# ConstantLED.net
KiCad netlist of a schematic drawn in Altium Designer
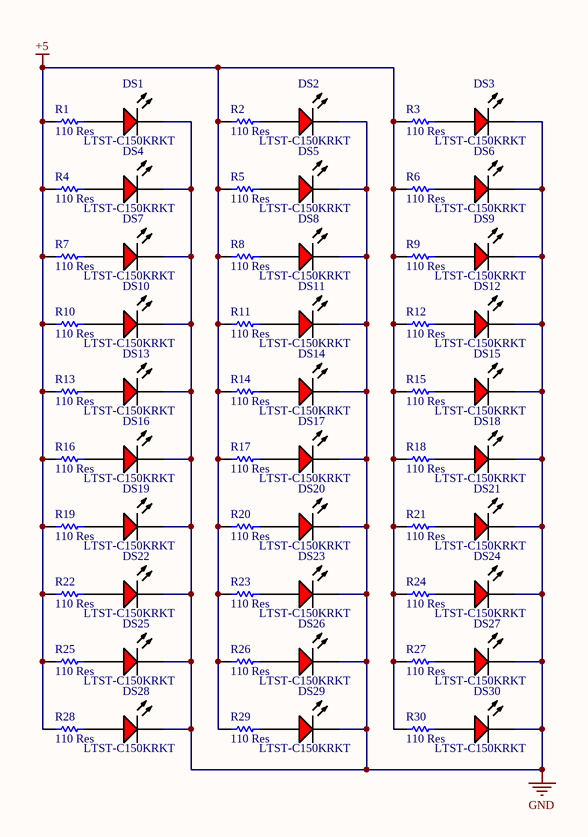
[diagram p0: ConstantLED.SchDoc]

(export (version "E")
  (design (tool "Eeschema 10.0.6"))
  (components
    (comp (ref "DS1")
      (value "LTST-C150KRKT")
      (footprint "LTST-C150KRKT_V")
      (description "LED Red, 62.5 mW, 50 mA, -30 to 85 degC, 2-Pin SMD, RoHS, Tape and Reel")
      (fields (field (name "MANUFACTURER") "Lite-On"))
      (libsource (lib "Altium Content Vault") (part "LED-RED-AK-2"))
    )
    (comp (ref "DS2")
      (value "LTST-C150KRKT")
      (footprint "LTST-C150KRKT_V")
      (description "LED Red, 62.5 mW, 50 mA, -30 to 85 degC, 2-Pin SMD, RoHS, Tape and Reel")
      (fields (field (name "MANUFACTURER") "Lite-On"))
      (libsource (lib "Altium Content Vault") (part "LED-RED-AK-2"))
    )
    (comp (ref "DS3")
      (value "LTST-C150KRKT")
      (footprint "LTST-C150KRKT_V")
      (description "LED Red, 62.5 mW, 50 mA, -30 to 85 degC, 2-Pin SMD, RoHS, Tape and Reel")
      (fields (field (name "MANUFACTURER") "Lite-On"))
      (libsource (lib "Altium Content Vault") (part "LED-RED-AK-2"))
    )
    (comp (ref "DS4")
      (value "LTST-C150KRKT")
      (footprint "LTST-C150KRKT_V")
      (description "LED Red, 62.5 mW, 50 mA, -30 to 85 degC, 2-Pin SMD, RoHS, Tape and Reel")
      (fields (field (name "MANUFACTURER") "Lite-On"))
      (libsource (lib "Altium Content Vault") (part "LED-RED-AK-2"))
    )
    (comp (ref "DS5")
      (value "LTST-C150KRKT")
      (footprint "LTST-C150KRKT_V")
      (description "LED Red, 62.5 mW, 50 mA, -30 to 85 degC, 2-Pin SMD, RoHS, Tape and Reel")
      (fields (field (name "MANUFACTURER") "Lite-On"))
      (libsource (lib "Altium Content Vault") (part "LED-RED-AK-2"))
    )
    (comp (ref "DS6")
      (value "LTST-C150KRKT")
      (footprint "LTST-C150KRKT_V")
      (description "LED Red, 62.5 mW, 50 mA, -30 to 85 degC, 2-Pin SMD, RoHS, Tape and Reel")
      (fields (field (name "MANUFACTURER") "Lite-On"))
      (libsource (lib "Altium Content Vault") (part "LED-RED-AK-2"))
    )
    (comp (ref "DS7")
      (value "LTST-C150KRKT")
      (footprint "LTST-C150KRKT_V")
      (description "LED Red, 62.5 mW, 50 mA, -30 to 85 degC, 2-Pin SMD, RoHS, Tape and Reel")
      (fields (field (name "MANUFACTURER") "Lite-On"))
      (libsource (lib "Altium Content Vault") (part "LED-RED-AK-2"))
    )
    (comp (ref "DS8")
      (value "LTST-C150KRKT")
      (footprint "LTST-C150KRKT_V")
      (description "LED Red, 62.5 mW, 50 mA, -30 to 85 degC, 2-Pin SMD, RoHS, Tape and Reel")
      (fields (field (name "MANUFACTURER") "Lite-On"))
      (libsource (lib "Altium Content Vault") (part "LED-RED-AK-2"))
    )
    (comp (ref "DS9")
      (value "LTST-C150KRKT")
      (footprint "LTST-C150KRKT_V")
      (description "LED Red, 62.5 mW, 50 mA, -30 to 85 degC, 2-Pin SMD, RoHS, Tape and Reel")
      (fields (field (name "MANUFACTURER") "Lite-On"))
      (libsource (lib "Altium Content Vault") (part "LED-RED-AK-2"))
    )
    (comp (ref "DS10")
      (value "LTST-C150KRKT")
      (footprint "LTST-C150KRKT_V")
      (description "LED Red, 62.5 mW, 50 mA, -30 to 85 degC, 2-Pin SMD, RoHS, Tape and Reel")
      (fields (field (name "MANUFACTURER") "Lite-On"))
      (libsource (lib "Altium Content Vault") (part "LED-RED-AK-2"))
    )
    (comp (ref "DS11")
      (value "LTST-C150KRKT")
      (footprint "LTST-C150KRKT_V")
      (description "LED Red, 62.5 mW, 50 mA, -30 to 85 degC, 2-Pin SMD, RoHS, Tape and Reel")
      (fields (field (name "MANUFACTURER") "Lite-On"))
      (libsource (lib "Altium Content Vault") (part "LED-RED-AK-2"))
    )
    (comp (ref "DS12")
      (value "LTST-C150KRKT")
      (footprint "LTST-C150KRKT_V")
      (description "LED Red, 62.5 mW, 50 mA, -30 to 85 degC, 2-Pin SMD, RoHS, Tape and Reel")
      (fields (field (name "MANUFACTURER") "Lite-On"))
      (libsource (lib "Altium Content Vault") (part "LED-RED-AK-2"))
    )
    (comp (ref "DS13")
      (value "LTST-C150KRKT")
      (footprint "LTST-C150KRKT_V")
      (description "LED Red, 62.5 mW, 50 mA, -30 to 85 degC, 2-Pin SMD, RoHS, Tape and Reel")
      (fields (field (name "MANUFACTURER") "Lite-On"))
      (libsource (lib "Altium Content Vault") (part "LED-RED-AK-2"))
    )
    (comp (ref "DS14")
      (value "LTST-C150KRKT")
      (footprint "LTST-C150KRKT_V")
      (description "LED Red, 62.5 mW, 50 mA, -30 to 85 degC, 2-Pin SMD, RoHS, Tape and Reel")
      (fields (field (name "MANUFACTURER") "Lite-On"))
      (libsource (lib "Altium Content Vault") (part "LED-RED-AK-2"))
    )
    (comp (ref "DS15")
      (value "LTST-C150KRKT")
      (footprint "LTST-C150KRKT_V")
      (description "LED Red, 62.5 mW, 50 mA, -30 to 85 degC, 2-Pin SMD, RoHS, Tape and Reel")
      (fields (field (name "MANUFACTURER") "Lite-On"))
      (libsource (lib "Altium Content Vault") (part "LED-RED-AK-2"))
    )
    (comp (ref "DS16")
      (value "LTST-C150KRKT")
      (footprint "LTST-C150KRKT_V")
      (description "LED Red, 62.5 mW, 50 mA, -30 to 85 degC, 2-Pin SMD, RoHS, Tape and Reel")
      (fields (field (name "MANUFACTURER") "Lite-On"))
      (libsource (lib "Altium Content Vault") (part "LED-RED-AK-2"))
    )
    (comp (ref "DS17")
      (value "LTST-C150KRKT")
      (footprint "LTST-C150KRKT_V")
      (description "LED Red, 62.5 mW, 50 mA, -30 to 85 degC, 2-Pin SMD, RoHS, Tape and Reel")
      (fields (field (name "MANUFACTURER") "Lite-On"))
      (libsource (lib "Altium Content Vault") (part "LED-RED-AK-2"))
    )
    (comp (ref "DS18")
      (value "LTST-C150KRKT")
      (footprint "LTST-C150KRKT_V")
      (description "LED Red, 62.5 mW, 50 mA, -30 to 85 degC, 2-Pin SMD, RoHS, Tape and Reel")
      (fields (field (name "MANUFACTURER") "Lite-On"))
      (libsource (lib "Altium Content Vault") (part "LED-RED-AK-2"))
    )
    (comp (ref "DS19")
      (value "LTST-C150KRKT")
      (footprint "LTST-C150KRKT_V")
      (description "LED Red, 62.5 mW, 50 mA, -30 to 85 degC, 2-Pin SMD, RoHS, Tape and Reel")
      (fields (field (name "MANUFACTURER") "Lite-On"))
      (libsource (lib "Altium Content Vault") (part "LED-RED-AK-2"))
    )
    (comp (ref "DS20")
      (value "LTST-C150KRKT")
      (footprint "LTST-C150KRKT_V")
      (description "LED Red, 62.5 mW, 50 mA, -30 to 85 degC, 2-Pin SMD, RoHS, Tape and Reel")
      (fields (field (name "MANUFACTURER") "Lite-On"))
      (libsource (lib "Altium Content Vault") (part "LED-RED-AK-2"))
    )
    (comp (ref "DS21")
      (value "LTST-C150KRKT")
      (footprint "LTST-C150KRKT_V")
      (description "LED Red, 62.5 mW, 50 mA, -30 to 85 degC, 2-Pin SMD, RoHS, Tape and Reel")
      (fields (field (name "MANUFACTURER") "Lite-On"))
      (libsource (lib "Altium Content Vault") (part "LED-RED-AK-2"))
    )
    (comp (ref "DS22")
      (value "LTST-C150KRKT")
      (footprint "LTST-C150KRKT_V")
      (description "LED Red, 62.5 mW, 50 mA, -30 to 85 degC, 2-Pin SMD, RoHS, Tape and Reel")
      (fields (field (name "MANUFACTURER") "Lite-On"))
      (libsource (lib "Altium Content Vault") (part "LED-RED-AK-2"))
    )
    (comp (ref "DS23")
      (value "LTST-C150KRKT")
      (footprint "LTST-C150KRKT_V")
      (description "LED Red, 62.5 mW, 50 mA, -30 to 85 degC, 2-Pin SMD, RoHS, Tape and Reel")
      (fields (field (name "MANUFACTURER") "Lite-On"))
      (libsource (lib "Altium Content Vault") (part "LED-RED-AK-2"))
    )
    (comp (ref "DS24")
      (value "LTST-C150KRKT")
      (footprint "LTST-C150KRKT_V")
      (description "LED Red, 62.5 mW, 50 mA, -30 to 85 degC, 2-Pin SMD, RoHS, Tape and Reel")
      (fields (field (name "MANUFACTURER") "Lite-On"))
      (libsource (lib "Altium Content Vault") (part "LED-RED-AK-2"))
    )
    (comp (ref "DS25")
      (value "LTST-C150KRKT")
      (footprint "LTST-C150KRKT_V")
      (description "LED Red, 62.5 mW, 50 mA, -30 to 85 degC, 2-Pin SMD, RoHS, Tape and Reel")
      (fields (field (name "MANUFACTURER") "Lite-On"))
      (libsource (lib "Altium Content Vault") (part "LED-RED-AK-2"))
    )
    (comp (ref "DS26")
      (value "LTST-C150KRKT")
      (footprint "LTST-C150KRKT_V")
      (description "LED Red, 62.5 mW, 50 mA, -30 to 85 degC, 2-Pin SMD, RoHS, Tape and Reel")
      (fields (field (name "MANUFACTURER") "Lite-On"))
      (libsource (lib "Altium Content Vault") (part "LED-RED-AK-2"))
    )
    (comp (ref "DS27")
      (value "LTST-C150KRKT")
      (footprint "LTST-C150KRKT_V")
      (description "LED Red, 62.5 mW, 50 mA, -30 to 85 degC, 2-Pin SMD, RoHS, Tape and Reel")
      (fields (field (name "MANUFACTURER") "Lite-On"))
      (libsource (lib "Altium Content Vault") (part "LED-RED-AK-2"))
    )
    (comp (ref "DS28")
      (value "LTST-C150KRKT")
      (footprint "LTST-C150KRKT_V")
      (description "LED Red, 62.5 mW, 50 mA, -30 to 85 degC, 2-Pin SMD, RoHS, Tape and Reel")
      (fields (field (name "MANUFACTURER") "Lite-On"))
      (libsource (lib "Altium Content Vault") (part "LED-RED-AK-2"))
    )
    (comp (ref "DS29")
      (value "LTST-C150KRKT")
      (footprint "LTST-C150KRKT_V")
      (description "LED Red, 62.5 mW, 50 mA, -30 to 85 degC, 2-Pin SMD, RoHS, Tape and Reel")
      (fields (field (name "MANUFACTURER") "Lite-On"))
      (libsource (lib "Altium Content Vault") (part "LED-RED-AK-2"))
    )
    (comp (ref "DS30")
      (value "LTST-C150KRKT")
      (footprint "LTST-C150KRKT_V")
      (description "LED Red, 62.5 mW, 50 mA, -30 to 85 degC, 2-Pin SMD, RoHS, Tape and Reel")
      (fields (field (name "MANUFACTURER") "Lite-On"))
      (libsource (lib "Altium Content Vault") (part "LED-RED-AK-2"))
    )
    (comp (ref "R1")
      (value "110 Res")
      (footprint "RESC3216X70X50LL05T20")
      (fields (field (name "PART NUMBER") "ERJ-8ENF1100V") (field (name "MANUFACTURER") "Panasonic"))
      (libsource (lib "Altium Content Vault") (part "RES"))
    )
    (comp (ref "R2")
      (value "110 Res")
      (footprint "RESC3216X70X50LL05T20")
      (fields (field (name "PART NUMBER") "ERJ-8ENF1100V") (field (name "MANUFACTURER") "Panasonic"))
      (libsource (lib "Altium Content Vault") (part "RES"))
    )
    (comp (ref "R3")
      (value "110 Res")
      (footprint "RESC3216X70X50LL05T20")
      (fields (field (name "PART NUMBER") "ERJ-8ENF1100V") (field (name "MANUFACTURER") "Panasonic"))
      (libsource (lib "Altium Content Vault") (part "RES"))
    )
    (comp (ref "R4")
      (value "110 Res")
      (footprint "RESC3216X70X50LL05T20")
      (fields (field (name "PART NUMBER") "ERJ-8ENF1100V") (field (name "MANUFACTURER") "Panasonic"))
      (libsource (lib "Altium Content Vault") (part "RES"))
    )
    (comp (ref "R5")
      (value "110 Res")
      (footprint "RESC3216X70X50LL05T20")
      (fields (field (name "PART NUMBER") "ERJ-8ENF1100V") (field (name "MANUFACTURER") "Panasonic"))
      (libsource (lib "Altium Content Vault") (part "RES"))
    )
    (comp (ref "R6")
      (value "110 Res")
      (footprint "RESC3216X70X50LL05T20")
      (fields (field (name "PART NUMBER") "ERJ-8ENF1100V") (field (name "MANUFACTURER") "Panasonic"))
      (libsource (lib "Altium Content Vault") (part "RES"))
    )
    (comp (ref "R7")
      (value "110 Res")
      (footprint "RESC3216X70X50LL05T20")
      (fields (field (name "PART NUMBER") "ERJ-8ENF1100V") (field (name "MANUFACTURER") "Panasonic"))
      (libsource (lib "Altium Content Vault") (part "RES"))
    )
    (comp (ref "R8")
      (value "110 Res")
      (footprint "RESC3216X70X50LL05T20")
      (fields (field (name "PART NUMBER") "ERJ-8ENF1100V") (field (name "MANUFACTURER") "Panasonic"))
      (libsource (lib "Altium Content Vault") (part "RES"))
    )
    (comp (ref "R9")
      (value "110 Res")
      (footprint "RESC3216X70X50LL05T20")
      (fields (field (name "PART NUMBER") "ERJ-8ENF1100V") (field (name "MANUFACTURER") "Panasonic"))
      (libsource (lib "Altium Content Vault") (part "RES"))
    )
    (comp (ref "R10")
      (value "110 Res")
      (footprint "RESC3216X70X50LL05T20")
      (fields (field (name "PART NUMBER") "ERJ-8ENF1100V") (field (name "MANUFACTURER") "Panasonic"))
      (libsource (lib "Altium Content Vault") (part "RES"))
    )
    (comp (ref "R11")
      (value "110 Res")
      (footprint "RESC3216X70X50LL05T20")
      (fields (field (name "PART NUMBER") "ERJ-8ENF1100V") (field (name "MANUFACTURER") "Panasonic"))
      (libsource (lib "Altium Content Vault") (part "RES"))
    )
    (comp (ref "R12")
      (value "110 Res")
      (footprint "RESC3216X70X50LL05T20")
      (fields (field (name "PART NUMBER") "ERJ-8ENF1100V") (field (name "MANUFACTURER") "Panasonic"))
      (libsource (lib "Altium Content Vault") (part "RES"))
    )
    (comp (ref "R13")
      (value "110 Res")
      (footprint "RESC3216X70X50LL05T20")
      (fields (field (name "PART NUMBER") "ERJ-8ENF1100V") (field (name "MANUFACTURER") "Panasonic"))
      (libsource (lib "Altium Content Vault") (part "RES"))
    )
    (comp (ref "R14")
      (value "110 Res")
      (footprint "RESC3216X70X50LL05T20")
      (fields (field (name "PART NUMBER") "ERJ-8ENF1100V") (field (name "MANUFACTURER") "Panasonic"))
      (libsource (lib "Altium Content Vault") (part "RES"))
    )
    (comp (ref "R15")
      (value "110 Res")
      (footprint "RESC3216X70X50LL05T20")
      (fields (field (name "PART NUMBER") "ERJ-8ENF1100V") (field (name "MANUFACTURER") "Panasonic"))
      (libsource (lib "Altium Content Vault") (part "RES"))
    )
    (comp (ref "R16")
      (value "110 Res")
      (footprint "RESC3216X70X50LL05T20")
      (fields (field (name "PART NUMBER") "ERJ-8ENF1100V") (field (name "MANUFACTURER") "Panasonic"))
      (libsource (lib "Altium Content Vault") (part "RES"))
    )
    (comp (ref "R17")
      (value "110 Res")
      (footprint "RESC3216X70X50LL05T20")
      (fields (field (name "PART NUMBER") "ERJ-8ENF1100V") (field (name "MANUFACTURER") "Panasonic"))
      (libsource (lib "Altium Content Vault") (part "RES"))
    )
    (comp (ref "R18")
      (value "110 Res")
      (footprint "RESC3216X70X50LL05T20")
      (fields (field (name "PART NUMBER") "ERJ-8ENF1100V") (field (name "MANUFACTURER") "Panasonic"))
      (libsource (lib "Altium Content Vault") (part "RES"))
    )
    (comp (ref "R19")
      (value "110 Res")
      (footprint "RESC3216X70X50LL05T20")
      (fields (field (name "PART NUMBER") "ERJ-8ENF1100V") (field (name "MANUFACTURER") "Panasonic"))
      (libsource (lib "Altium Content Vault") (part "RES"))
    )
    (comp (ref "R20")
      (value "110 Res")
      (footprint "RESC3216X70X50LL05T20")
      (fields (field (name "PART NUMBER") "ERJ-8ENF1100V") (field (name "MANUFACTURER") "Panasonic"))
      (libsource (lib "Altium Content Vault") (part "RES"))
    )
    (comp (ref "R21")
      (value "110 Res")
      (footprint "RESC3216X70X50LL05T20")
      (fields (field (name "PART NUMBER") "ERJ-8ENF1100V") (field (name "MANUFACTURER") "Panasonic"))
      (libsource (lib "Altium Content Vault") (part "RES"))
    )
    (comp (ref "R22")
      (value "110 Res")
      (footprint "RESC3216X70X50LL05T20")
      (fields (field (name "PART NUMBER") "ERJ-8ENF1100V") (field (name "MANUFACTURER") "Panasonic"))
      (libsource (lib "Altium Content Vault") (part "RES"))
    )
    (comp (ref "R23")
      (value "110 Res")
      (footprint "RESC3216X70X50LL05T20")
      (fields (field (name "PART NUMBER") "ERJ-8ENF1100V") (field (name "MANUFACTURER") "Panasonic"))
      (libsource (lib "Altium Content Vault") (part "RES"))
    )
    (comp (ref "R24")
      (value "110 Res")
      (footprint "RESC3216X70X50LL05T20")
      (fields (field (name "PART NUMBER") "ERJ-8ENF1100V") (field (name "MANUFACTURER") "Panasonic"))
      (libsource (lib "Altium Content Vault") (part "RES"))
    )
    (comp (ref "R25")
      (value "110 Res")
      (footprint "RESC3216X70X50LL05T20")
      (fields (field (name "PART NUMBER") "ERJ-8ENF1100V") (field (name "MANUFACTURER") "Panasonic"))
      (libsource (lib "Altium Content Vault") (part "RES"))
    )
    (comp (ref "R26")
      (value "110 Res")
      (footprint "RESC3216X70X50LL05T20")
      (fields (field (name "PART NUMBER") "ERJ-8ENF1100V") (field (name "MANUFACTURER") "Panasonic"))
      (libsource (lib "Altium Content Vault") (part "RES"))
    )
    (comp (ref "R27")
      (value "110 Res")
      (footprint "RESC3216X70X50LL05T20")
      (fields (field (name "PART NUMBER") "ERJ-8ENF1100V") (field (name "MANUFACTURER") "Panasonic"))
      (libsource (lib "Altium Content Vault") (part "RES"))
    )
    (comp (ref "R28")
      (value "110 Res")
      (footprint "RESC3216X70X50LL05T20")
      (fields (field (name "PART NUMBER") "ERJ-8ENF1100V") (field (name "MANUFACTURER") "Panasonic"))
      (libsource (lib "Altium Content Vault") (part "RES"))
    )
    (comp (ref "R29")
      (value "110 Res")
      (footprint "RESC3216X70X50LL05T20")
      (fields (field (name "PART NUMBER") "ERJ-8ENF1100V") (field (name "MANUFACTURER") "Panasonic"))
      (libsource (lib "Altium Content Vault") (part "RES"))
    )
    (comp (ref "R30")
      (value "110 Res")
      (footprint "RESC3216X70X50LL05T20")
      (fields (field (name "PART NUMBER") "ERJ-8ENF1100V") (field (name "MANUFACTURER") "Panasonic"))
      (libsource (lib "Altium Content Vault") (part "RES"))
    )
  )
  (nets
    (net (code "1") (name "+5") (class "Default")
      (node (ref "R1") (pin "1") (pinfunction "1_1") (pintype "passive"))
      (node (ref "R10") (pin "1") (pinfunction "1_1") (pintype "passive"))
      (node (ref "R11") (pin "1") (pinfunction "1_1") (pintype "passive"))
      (node (ref "R12") (pin "1") (pinfunction "1_1") (pintype "passive"))
      (node (ref "R13") (pin "1") (pinfunction "1_1") (pintype "passive"))
      (node (ref "R14") (pin "1") (pinfunction "1_1") (pintype "passive"))
      (node (ref "R15") (pin "1") (pinfunction "1_1") (pintype "passive"))
      (node (ref "R16") (pin "1") (pinfunction "1_1") (pintype "passive"))
      (node (ref "R17") (pin "1") (pinfunction "1_1") (pintype "passive"))
      (node (ref "R18") (pin "1") (pinfunction "1_1") (pintype "passive"))
      (node (ref "R19") (pin "1") (pinfunction "1_1") (pintype "passive"))
      (node (ref "R2") (pin "1") (pinfunction "1_1") (pintype "passive"))
      (node (ref "R20") (pin "1") (pinfunction "1_1") (pintype "passive"))
      (node (ref "R21") (pin "1") (pinfunction "1_1") (pintype "passive"))
      (node (ref "R22") (pin "1") (pinfunction "1_1") (pintype "passive"))
      (node (ref "R23") (pin "1") (pinfunction "1_1") (pintype "passive"))
      (node (ref "R24") (pin "1") (pinfunction "1_1") (pintype "passive"))
      (node (ref "R25") (pin "1") (pinfunction "1_1") (pintype "passive"))
      (node (ref "R26") (pin "1") (pinfunction "1_1") (pintype "passive"))
      (node (ref "R27") (pin "1") (pinfunction "1_1") (pintype "passive"))
      (node (ref "R28") (pin "1") (pinfunction "1_1") (pintype "passive"))
      (node (ref "R29") (pin "1") (pinfunction "1_1") (pintype "passive"))
      (node (ref "R3") (pin "1") (pinfunction "1_1") (pintype "passive"))
      (node (ref "R30") (pin "1") (pinfunction "1_1") (pintype "passive"))
      (node (ref "R4") (pin "1") (pinfunction "1_1") (pintype "passive"))
      (node (ref "R5") (pin "1") (pinfunction "1_1") (pintype "passive"))
      (node (ref "R6") (pin "1") (pinfunction "1_1") (pintype "passive"))
      (node (ref "R7") (pin "1") (pinfunction "1_1") (pintype "passive"))
      (node (ref "R8") (pin "1") (pinfunction "1_1") (pintype "passive"))
      (node (ref "R9") (pin "1") (pinfunction "1_1") (pintype "passive"))
    )
    (net (code "2") (name "GND") (class "Default")
      (node (ref "DS1") (pin "2") (pinfunction "K_2") (pintype "passive"))
      (node (ref "DS10") (pin "2") (pinfunction "K_2") (pintype "passive"))
      (node (ref "DS11") (pin "2") (pinfunction "K_2") (pintype "passive"))
      (node (ref "DS12") (pin "2") (pinfunction "K_2") (pintype "passive"))
      (node (ref "DS13") (pin "2") (pinfunction "K_2") (pintype "passive"))
      (node (ref "DS14") (pin "2") (pinfunction "K_2") (pintype "passive"))
      (node (ref "DS15") (pin "2") (pinfunction "K_2") (pintype "passive"))
      (node (ref "DS16") (pin "2") (pinfunction "K_2") (pintype "passive"))
      (node (ref "DS17") (pin "2") (pinfunction "K_2") (pintype "passive"))
      (node (ref "DS18") (pin "2") (pinfunction "K_2") (pintype "passive"))
      (node (ref "DS19") (pin "2") (pinfunction "K_2") (pintype "passive"))
      (node (ref "DS2") (pin "2") (pinfunction "K_2") (pintype "passive"))
      (node (ref "DS20") (pin "2") (pinfunction "K_2") (pintype "passive"))
      (node (ref "DS21") (pin "2") (pinfunction "K_2") (pintype "passive"))
      (node (ref "DS22") (pin "2") (pinfunction "K_2") (pintype "passive"))
      (node (ref "DS23") (pin "2") (pinfunction "K_2") (pintype "passive"))
      (node (ref "DS24") (pin "2") (pinfunction "K_2") (pintype "passive"))
      (node (ref "DS25") (pin "2") (pinfunction "K_2") (pintype "passive"))
      (node (ref "DS26") (pin "2") (pinfunction "K_2") (pintype "passive"))
      (node (ref "DS27") (pin "2") (pinfunction "K_2") (pintype "passive"))
      (node (ref "DS28") (pin "2") (pinfunction "K_2") (pintype "passive"))
      (node (ref "DS29") (pin "2") (pinfunction "K_2") (pintype "passive"))
      (node (ref "DS3") (pin "2") (pinfunction "K_2") (pintype "passive"))
      (node (ref "DS30") (pin "2") (pinfunction "K_2") (pintype "passive"))
      (node (ref "DS4") (pin "2") (pinfunction "K_2") (pintype "passive"))
      (node (ref "DS5") (pin "2") (pinfunction "K_2") (pintype "passive"))
      (node (ref "DS6") (pin "2") (pinfunction "K_2") (pintype "passive"))
      (node (ref "DS7") (pin "2") (pinfunction "K_2") (pintype "passive"))
      (node (ref "DS8") (pin "2") (pinfunction "K_2") (pintype "passive"))
      (node (ref "DS9") (pin "2") (pinfunction "K_2") (pintype "passive"))
    )
    (net (code "3") (name "Net-(DS1-A)") (class "Default")
      (node (ref "DS1") (pin "1") (pinfunction "A_1") (pintype "passive"))
      (node (ref "R1") (pin "2") (pinfunction "2_2") (pintype "passive"))
    )
    (net (code "4") (name "Net-(DS2-A)") (class "Default")
      (node (ref "DS2") (pin "1") (pinfunction "A_1") (pintype "passive"))
      (node (ref "R2") (pin "2") (pinfunction "2_2") (pintype "passive"))
    )
    (net (code "5") (name "Net-(DS3-A)") (class "Default")
      (node (ref "DS3") (pin "1") (pinfunction "A_1") (pintype "passive"))
      (node (ref "R3") (pin "2") (pinfunction "2_2") (pintype "passive"))
    )
    (net (code "6") (name "Net-(DS4-A)") (class "Default")
      (node (ref "DS4") (pin "1") (pinfunction "A_1") (pintype "passive"))
      (node (ref "R4") (pin "2") (pinfunction "2_2") (pintype "passive"))
    )
    (net (code "7") (name "Net-(DS5-A)") (class "Default")
      (node (ref "DS5") (pin "1") (pinfunction "A_1") (pintype "passive"))
      (node (ref "R5") (pin "2") (pinfunction "2_2") (pintype "passive"))
    )
    (net (code "8") (name "Net-(DS6-A)") (class "Default")
      (node (ref "DS6") (pin "1") (pinfunction "A_1") (pintype "passive"))
      (node (ref "R6") (pin "2") (pinfunction "2_2") (pintype "passive"))
    )
    (net (code "9") (name "Net-(DS7-A)") (class "Default")
      (node (ref "DS7") (pin "1") (pinfunction "A_1") (pintype "passive"))
      (node (ref "R7") (pin "2") (pinfunction "2_2") (pintype "passive"))
    )
    (net (code "10") (name "Net-(DS8-A)") (class "Default")
      (node (ref "DS8") (pin "1") (pinfunction "A_1") (pintype "passive"))
      (node (ref "R8") (pin "2") (pinfunction "2_2") (pintype "passive"))
    )
    (net (code "11") (name "Net-(DS9-A)") (class "Default")
      (node (ref "DS9") (pin "1") (pinfunction "A_1") (pintype "passive"))
      (node (ref "R9") (pin "2") (pinfunction "2_2") (pintype "passive"))
    )
    (net (code "12") (name "Net-(DS10-A)") (class "Default")
      (node (ref "DS10") (pin "1") (pinfunction "A_1") (pintype "passive"))
      (node (ref "R10") (pin "2") (pinfunction "2_2") (pintype "passive"))
    )
    (net (code "13") (name "Net-(DS11-A)") (class "Default")
      (node (ref "DS11") (pin "1") (pinfunction "A_1") (pintype "passive"))
      (node (ref "R11") (pin "2") (pinfunction "2_2") (pintype "passive"))
    )
    (net (code "14") (name "Net-(DS12-A)") (class "Default")
      (node (ref "DS12") (pin "1") (pinfunction "A_1") (pintype "passive"))
      (node (ref "R12") (pin "2") (pinfunction "2_2") (pintype "passive"))
    )
    (net (code "15") (name "Net-(DS13-A)") (class "Default")
      (node (ref "DS13") (pin "1") (pinfunction "A_1") (pintype "passive"))
      (node (ref "R13") (pin "2") (pinfunction "2_2") (pintype "passive"))
    )
    (net (code "16") (name "Net-(DS14-A)") (class "Default")
      (node (ref "DS14") (pin "1") (pinfunction "A_1") (pintype "passive"))
      (node (ref "R14") (pin "2") (pinfunction "2_2") (pintype "passive"))
    )
    (net (code "17") (name "Net-(DS15-A)") (class "Default")
      (node (ref "DS15") (pin "1") (pinfunction "A_1") (pintype "passive"))
      (node (ref "R15") (pin "2") (pinfunction "2_2") (pintype "passive"))
    )
    (net (code "18") (name "Net-(DS16-A)") (class "Default")
      (node (ref "DS16") (pin "1") (pinfunction "A_1") (pintype "passive"))
      (node (ref "R16") (pin "2") (pinfunction "2_2") (pintype "passive"))
    )
    (net (code "19") (name "Net-(DS17-A)") (class "Default")
      (node (ref "DS17") (pin "1") (pinfunction "A_1") (pintype "passive"))
      (node (ref "R17") (pin "2") (pinfunction "2_2") (pintype "passive"))
    )
    (net (code "20") (name "Net-(DS18-A)") (class "Default")
      (node (ref "DS18") (pin "1") (pinfunction "A_1") (pintype "passive"))
      (node (ref "R18") (pin "2") (pinfunction "2_2") (pintype "passive"))
    )
    (net (code "21") (name "Net-(DS19-A)") (class "Default")
      (node (ref "DS19") (pin "1") (pinfunction "A_1") (pintype "passive"))
      (node (ref "R19") (pin "2") (pinfunction "2_2") (pintype "passive"))
    )
    (net (code "22") (name "Net-(DS20-A)") (class "Default")
      (node (ref "DS20") (pin "1") (pinfunction "A_1") (pintype "passive"))
      (node (ref "R20") (pin "2") (pinfunction "2_2") (pintype "passive"))
    )
    (net (code "23") (name "Net-(DS21-A)") (class "Default")
      (node (ref "DS21") (pin "1") (pinfunction "A_1") (pintype "passive"))
      (node (ref "R21") (pin "2") (pinfunction "2_2") (pintype "passive"))
    )
    (net (code "24") (name "Net-(DS22-A)") (class "Default")
      (node (ref "DS22") (pin "1") (pinfunction "A_1") (pintype "passive"))
      (node (ref "R22") (pin "2") (pinfunction "2_2") (pintype "passive"))
    )
    (net (code "25") (name "Net-(DS23-A)") (class "Default")
      (node (ref "DS23") (pin "1") (pinfunction "A_1") (pintype "passive"))
      (node (ref "R23") (pin "2") (pinfunction "2_2") (pintype "passive"))
    )
    (net (code "26") (name "Net-(DS24-A)") (class "Default")
      (node (ref "DS24") (pin "1") (pinfunction "A_1") (pintype "passive"))
      (node (ref "R24") (pin "2") (pinfunction "2_2") (pintype "passive"))
    )
    (net (code "27") (name "Net-(DS25-A)") (class "Default")
      (node (ref "DS25") (pin "1") (pinfunction "A_1") (pintype "passive"))
      (node (ref "R25") (pin "2") (pinfunction "2_2") (pintype "passive"))
    )
    (net (code "28") (name "Net-(DS26-A)") (class "Default")
      (node (ref "DS26") (pin "1") (pinfunction "A_1") (pintype "passive"))
      (node (ref "R26") (pin "2") (pinfunction "2_2") (pintype "passive"))
    )
    (net (code "29") (name "Net-(DS27-A)") (class "Default")
      (node (ref "DS27") (pin "1") (pinfunction "A_1") (pintype "passive"))
      (node (ref "R27") (pin "2") (pinfunction "2_2") (pintype "passive"))
    )
    (net (code "30") (name "Net-(DS28-A)") (class "Default")
      (node (ref "DS28") (pin "1") (pinfunction "A_1") (pintype "passive"))
      (node (ref "R28") (pin "2") (pinfunction "2_2") (pintype "passive"))
    )
    (net (code "31") (name "Net-(DS29-A)") (class "Default")
      (node (ref "DS29") (pin "1") (pinfunction "A_1") (pintype "passive"))
      (node (ref "R29") (pin "2") (pinfunction "2_2") (pintype "passive"))
    )
    (net (code "32") (name "Net-(DS30-A)") (class "Default")
      (node (ref "DS30") (pin "1") (pinfunction "A_1") (pintype "passive"))
      (node (ref "R30") (pin "2") (pinfunction "2_2") (pintype "passive"))
    )
  )
)
